# eth_100base-tx_magnetics.net
KiCad netlist of a schematic drawn in Altium Designer
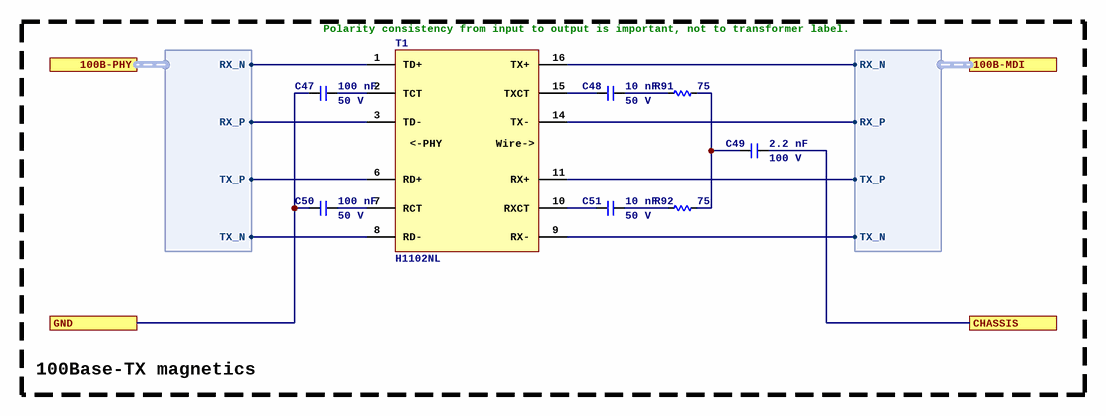
[diagram p0: eth_100base-tx_magnetics.SchDoc]

(export (version "E")
  (design (tool "Eeschema 10.0.6"))
  (components
    (comp (ref "C47")
      (value "CL05B104KB54PNC")
      (footprint "C0402")
      (fields
        (field (name "CAPACITANCE") "100 nF")
        (field (name "MANUFACTURER") "Samsung Electro-Mechanics")
        (field (name "VOLTAGE RATING") "50 V")
      )
      (libsource (lib "database") (part "__template_cap"))
    )
    (comp (ref "C48")
      (value "CL05B103KB5NNNC")
      (footprint "C0402")
      (fields
        (field (name "CAPACITANCE") "10 nF")
        (field (name "MANUFACTURER") "Samsung Electro-Mechanics")
        (field (name "VOLTAGE RATING") "50 V")
      )
      (libsource (lib "database") (part "__template_cap"))
    )
    (comp (ref "C49")
      (value "CC0402KRX7R0BB222")
      (footprint "C0402")
      (fields
        (field (name "CAPACITANCE") "2.2 nF")
        (field (name "MANUFACTURER") "YAGEO")
        (field (name "VOLTAGE RATING") "100 V")
      )
      (libsource (lib "database") (part "__template_cap"))
    )
    (comp (ref "C50")
      (value "CL05B104KB54PNC")
      (footprint "C0402")
      (fields
        (field (name "CAPACITANCE") "100 nF")
        (field (name "MANUFACTURER") "Samsung Electro-Mechanics")
        (field (name "VOLTAGE RATING") "50 V")
      )
      (libsource (lib "database") (part "__template_cap"))
    )
    (comp (ref "C51")
      (value "CL05B103KB5NNNC")
      (footprint "C0402")
      (fields
        (field (name "CAPACITANCE") "10 nF")
        (field (name "MANUFACTURER") "Samsung Electro-Mechanics")
        (field (name "VOLTAGE RATING") "50 V")
      )
      (libsource (lib "database") (part "__template_cap"))
    )
    (comp (ref "R91")
      (value "75")
      (footprint "R0402")
      (fields
        (field (name "TOLERANCE") "1%")
        (field (name "MANUFACTURER PART NUMBER") "0402WGF750JTCE")
        (field (name "MANUFACTURER") "UNI-ROYAL(Uniroyal Elec)")
      )
      (libsource (lib "database") (part "__template_resistor"))
    )
    (comp (ref "R92")
      (value "75")
      (footprint "R0402")
      (fields
        (field (name "TOLERANCE") "1%")
        (field (name "MANUFACTURER PART NUMBER") "0402WGF750JTCE")
        (field (name "MANUFACTURER") "UNI-ROYAL(Uniroyal Elec)")
      )
      (libsource (lib "database") (part "__template_resistor"))
    )
    (comp (ref "T1")
      (value "H1102NL")
      (footprint "EPCOS_LAN_MODULE")
      (description "MODULE XFRMR SGL ETHR LAN 16SOIC")
      (fields
        (field (name "MANUFACTURER") "Pulse Electronics Corporation")
        (field (name "MANUFACTURER PART NUMBER") "H1102NL")
      )
      (libsource (lib "database") (part "H1102NL"))
    )
  )
  (nets
    (net (code "2") (name "/CHASSIS") (class "Default") (node (ref "C49") (pin "2") (pintype "passive")))
    (net (code "3") (name "/GND") (class "Default")
      (node (ref "C47") (pin "2") (pintype "passive"))
      (node (ref "C50") (pin "2") (pintype "passive"))
    )
    (net (code "5") (name "Net-(C48-Pad2)") (class "Default")
      (node (ref "C48") (pin "2") (pintype "passive"))
      (node (ref "R91") (pin "2") (pintype "passive"))
    )
    (net (code "6") (name "Net-(C49-Pad1)") (class "Default")
      (node (ref "C49") (pin "1") (pintype "passive"))
      (node (ref "R91") (pin "1") (pintype "passive"))
      (node (ref "R92") (pin "1") (pintype "passive"))
    )
    (net (code "7") (name "Net-(C51-Pad2)") (class "Default")
      (node (ref "C51") (pin "2") (pintype "passive"))
      (node (ref "R92") (pin "2") (pintype "passive"))
    )
    (net (code "8") (name "Net-(T1-RCT)") (class "Default")
      (node (ref "C50") (pin "1") (pintype "passive"))
      (node (ref "T1") (pin "7") (pinfunction "RCT_7") (pintype "passive"))
    )
    (net (code "9") (name "Net-(T1-RXCT)") (class "Default")
      (node (ref "C51") (pin "1") (pintype "passive"))
      (node (ref "T1") (pin "10") (pinfunction "RXCT_10") (pintype "passive"))
    )
    (net (code "10") (name "Net-(T1-TCT)") (class "Default")
      (node (ref "C47") (pin "1") (pintype "passive"))
      (node (ref "T1") (pin "2") (pinfunction "TCT_2") (pintype "passive"))
    )
    (net (code "11") (name "Net-(T1-TXCT)") (class "Default")
      (node (ref "C48") (pin "1") (pintype "passive"))
      (node (ref "T1") (pin "15") (pinfunction "TXCT_15") (pintype "passive"))
    )
    (net (code "12") (name "unconnected-(T1-RD+-Pad6)") (class "Default")
      (node (ref "T1") (pin "6") (pinfunction "RD+_6") (pintype "passive"))
    )
    (net (code "13") (name "unconnected-(T1-RD--Pad8)") (class "Default")
      (node (ref "T1") (pin "8") (pinfunction "RD-_8") (pintype "passive"))
    )
    (net (code "14") (name "unconnected-(T1-RX+-Pad11)") (class "Default")
      (node (ref "T1") (pin "11") (pinfunction "RX+_11") (pintype "passive"))
    )
    (net (code "15") (name "unconnected-(T1-RX--Pad9)") (class "Default")
      (node (ref "T1") (pin "9") (pinfunction "RX-_9") (pintype "passive"))
    )
    (net (code "16") (name "unconnected-(T1-TD+-Pad1)") (class "Default")
      (node (ref "T1") (pin "1") (pinfunction "TD+_1") (pintype "passive"))
    )
    (net (code "17") (name "unconnected-(T1-TD--Pad3)") (class "Default")
      (node (ref "T1") (pin "3") (pinfunction "TD-_3") (pintype "passive"))
    )
    (net (code "18") (name "unconnected-(T1-TX+-Pad16)") (class "Default")
      (node (ref "T1") (pin "16") (pinfunction "TX+_16") (pintype "passive"))
    )
    (net (code "19") (name "unconnected-(T1-TX--Pad14)") (class "Default")
      (node (ref "T1") (pin "14") (pinfunction "TX-_14") (pintype "passive"))
    )
  )
)
